# 04_HDMI_Interface.net
KiCad netlist of a schematic drawn in Altium Designer
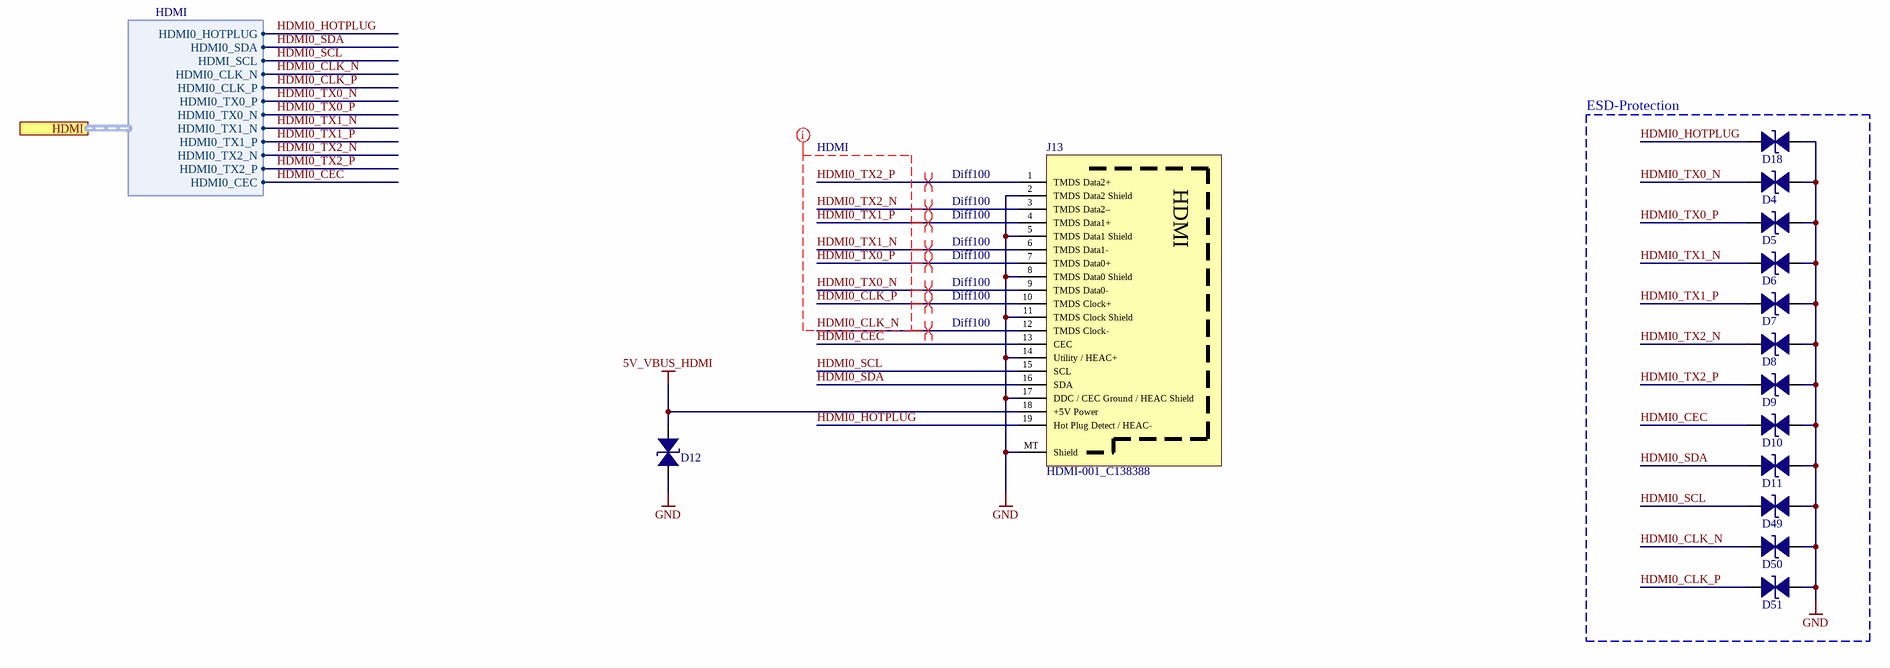
[diagram p0: 04_HDMI_Interface.SchDoc]

(export (version "E")
  (design (tool "Eeschema 10.0.6"))
  (components
    (comp (ref "D4")
      (value "CESDP0402UC5VB")
      (footprint "Protec:TVS_0402")
      (description "Low Capacitance ESD Protection Diode 0402")
      (libsource (lib "Protec") (part "CESDP0402UC5VB_TVS Diode 0402"))
    )
    (comp (ref "D5")
      (value "CESDP0402UC5VB")
      (footprint "Protec:TVS_0402")
      (description "Low Capacitance ESD Protection Diode 0402")
      (libsource (lib "Protec") (part "CESDP0402UC5VB_TVS Diode 0402"))
    )
    (comp (ref "D6")
      (value "CESDP0402UC5VB")
      (footprint "Protec:TVS_0402")
      (description "Low Capacitance ESD Protection Diode 0402")
      (libsource (lib "Protec") (part "CESDP0402UC5VB_TVS Diode 0402"))
    )
    (comp (ref "D7")
      (value "CESDP0402UC5VB")
      (footprint "Protec:TVS_0402")
      (description "Low Capacitance ESD Protection Diode 0402")
      (libsource (lib "Protec") (part "CESDP0402UC5VB_TVS Diode 0402"))
    )
    (comp (ref "D8")
      (value "CESDP0402UC5VB")
      (footprint "Protec:TVS_0402")
      (description "Low Capacitance ESD Protection Diode 0402")
      (libsource (lib "Protec") (part "CESDP0402UC5VB_TVS Diode 0402"))
    )
    (comp (ref "D9")
      (value "CESDP0402UC5VB")
      (footprint "Protec:TVS_0402")
      (description "Low Capacitance ESD Protection Diode 0402")
      (libsource (lib "Protec") (part "CESDP0402UC5VB_TVS Diode 0402"))
    )
    (comp (ref "D10")
      (value "CESDP0402UC5VB")
      (footprint "Protec:TVS_0402")
      (description "Low Capacitance ESD Protection Diode 0402")
      (libsource (lib "Protec") (part "CESDP0402UC5VB_TVS Diode 0402"))
    )
    (comp (ref "D11")
      (value "CESDP0402UC5VB")
      (footprint "Protec:TVS_0402")
      (description "Low Capacitance ESD Protection Diode 0402")
      (libsource (lib "Protec") (part "CESDP0402UC5VB_TVS Diode 0402"))
    )
    (comp (ref "D12")
      (value "CESDP0402UC5VB")
      (footprint "Protec:TVS_0402")
      (description "Low Capacitance ESD Protection Diode 0402")
      (libsource (lib "Protec") (part "CESDP0402UC5VB_TVS Diode 0402"))
    )
    (comp (ref "D18")
      (value "CESDP0402UC5VB")
      (footprint "Protec:TVS_0402")
      (description "Low Capacitance ESD Protection Diode 0402")
      (libsource (lib "Protec") (part "CESDP0402UC5VB_TVS Diode 0402"))
    )
    (comp (ref "D49")
      (value "CESDP0402UC5VB")
      (footprint "Protec:TVS_0402")
      (description "Low Capacitance ESD Protection Diode 0402")
      (libsource (lib "Protec") (part "CESDP0402UC5VB_TVS Diode 0402"))
    )
    (comp (ref "D50")
      (value "CESDP0402UC5VB")
      (footprint "Protec:TVS_0402")
      (description "Low Capacitance ESD Protection Diode 0402")
      (libsource (lib "Protec") (part "CESDP0402UC5VB_TVS Diode 0402"))
    )
    (comp (ref "D51")
      (value "CESDP0402UC5VB")
      (footprint "Protec:TVS_0402")
      (description "Low Capacitance ESD Protection Diode 0402")
      (libsource (lib "Protec") (part "CESDP0402UC5VB_TVS Diode 0402"))
    )
    (comp (ref "J13")
      (value "HDMI-001_C138388")
      (footprint "COnn:BOOMELE HDMI-001")
      (description "HDMI Connector Female 19 Pin LCSC C138388")
      (libsource (lib "Conn") (part "HDMI-001_HDMI Connector 19Pin SMD"))
    )
  )
  (nets
    (net (code "2") (name "/HDMI0_CEC") (class "Default")
      (node (ref "D10") (pin "1") (pinfunction "1_1") (pintype "passive"))
      (node (ref "J13") (pin "13") (pinfunction "CEC_13") (pintype "passive"))
    )
    (net (code "3") (name "/HDMI0_CLK_N") (class "Default")
      (node (ref "D50") (pin "1") (pinfunction "1_1") (pintype "passive"))
      (node (ref "J13") (pin "12") (pinfunction "TMDS_Clock-_12") (pintype "passive"))
    )
    (net (code "4") (name "/HDMI0_CLK_P") (class "Default")
      (node (ref "D51") (pin "1") (pinfunction "1_1") (pintype "passive"))
      (node (ref "J13") (pin "10") (pinfunction "TMDS_Clock+_10") (pintype "passive"))
    )
    (net (code "5") (name "/HDMI0_HOTPLUG") (class "Default")
      (node (ref "D18") (pin "1") (pinfunction "1_1") (pintype "passive"))
      (node (ref "J13") (pin "19") (pinfunction "Hot_Plug_Detect_/_HEAC-_19") (pintype "passive"))
    )
    (net (code "6") (name "/HDMI0_SCL") (class "Default")
      (node (ref "D49") (pin "1") (pinfunction "1_1") (pintype "passive"))
      (node (ref "J13") (pin "15") (pinfunction "SCL_15") (pintype "passive"))
    )
    (net (code "7") (name "/HDMI0_SDA") (class "Default")
      (node (ref "D11") (pin "1") (pinfunction "1_1") (pintype "passive"))
      (node (ref "J13") (pin "16") (pinfunction "SDA_16") (pintype "passive"))
    )
    (net (code "8") (name "/HDMI0_TX0_N") (class "Default")
      (node (ref "D4") (pin "1") (pinfunction "1_1") (pintype "passive"))
      (node (ref "J13") (pin "9") (pinfunction "TMDS_Data0-_9") (pintype "passive"))
    )
    (net (code "9") (name "/HDMI0_TX0_P") (class "Default")
      (node (ref "D5") (pin "1") (pinfunction "1_1") (pintype "passive"))
      (node (ref "J13") (pin "7") (pinfunction "TMDS_Data0+_7") (pintype "passive"))
    )
    (net (code "10") (name "/HDMI0_TX1_N") (class "Default")
      (node (ref "D6") (pin "1") (pinfunction "1_1") (pintype "passive"))
      (node (ref "J13") (pin "6") (pinfunction "TMDS_Data1-_6") (pintype "passive"))
    )
    (net (code "11") (name "/HDMI0_TX1_P") (class "Default")
      (node (ref "D7") (pin "1") (pinfunction "1_1") (pintype "passive"))
      (node (ref "J13") (pin "4") (pinfunction "TMDS_Data1+_4") (pintype "passive"))
    )
    (net (code "12") (name "/HDMI0_TX2_N") (class "Default")
      (node (ref "D8") (pin "1") (pinfunction "1_1") (pintype "passive"))
      (node (ref "J13") (pin "3") (pinfunction "TMDS_Data2–_3") (pintype "passive"))
    )
    (net (code "13") (name "/HDMI0_TX2_P") (class "Default")
      (node (ref "D9") (pin "1") (pinfunction "1_1") (pintype "passive"))
      (node (ref "J13") (pin "1") (pinfunction "TMDS_Data2+_1") (pintype "passive"))
    )
    (net (code "15") (name "5V_VBUS_HDMI") (class "Default")
      (node (ref "D12") (pin "2") (pinfunction "2_2") (pintype "passive"))
      (node (ref "J13") (pin "18") (pinfunction "+5V_Power_18") (pintype "passive"))
    )
    (net (code "16") (name "GND") (class "Default")
      (node (ref "D10") (pin "2") (pinfunction "2_2") (pintype "passive"))
      (node (ref "D11") (pin "2") (pinfunction "2_2") (pintype "passive"))
      (node (ref "D12") (pin "1") (pinfunction "1_1") (pintype "passive"))
      (node (ref "D18") (pin "2") (pinfunction "2_2") (pintype "passive"))
      (node (ref "D4") (pin "2") (pinfunction "2_2") (pintype "passive"))
      (node (ref "D49") (pin "2") (pinfunction "2_2") (pintype "passive"))
      (node (ref "D5") (pin "2") (pinfunction "2_2") (pintype "passive"))
      (node (ref "D50") (pin "2") (pinfunction "2_2") (pintype "passive"))
      (node (ref "D51") (pin "2") (pinfunction "2_2") (pintype "passive"))
      (node (ref "D6") (pin "2") (pinfunction "2_2") (pintype "passive"))
      (node (ref "D7") (pin "2") (pinfunction "2_2") (pintype "passive"))
      (node (ref "D8") (pin "2") (pinfunction "2_2") (pintype "passive"))
      (node (ref "D9") (pin "2") (pinfunction "2_2") (pintype "passive"))
      (node (ref "J13") (pin "11") (pinfunction "TMDS_Clock_Shield_11") (pintype "passive"))
      (node (ref "J13") (pin "14") (pinfunction "Utility_/_HEAC+_14") (pintype "passive"))
      (node (ref "J13") (pin "17") (pinfunction "DDC_/_CEC_Ground_/_HEAC_Shield_17") (pintype "passive"))
      (node (ref "J13") (pin "2") (pinfunction "TMDS_Data2_Shield_2") (pintype "passive"))
      (node (ref "J13") (pin "5") (pinfunction "TMDS_Data1_Shield_5") (pintype "passive"))
      (node (ref "J13") (pin "8") (pinfunction "TMDS_Data0_Shield_8") (pintype "passive"))
      (node (ref "J13") (pin "MT") (pinfunction "Shield_MT") (pintype "passive"))
    )
  )
)
